# pcb_eagle.net
KiCad netlist of a schematic drawn in EAGLE
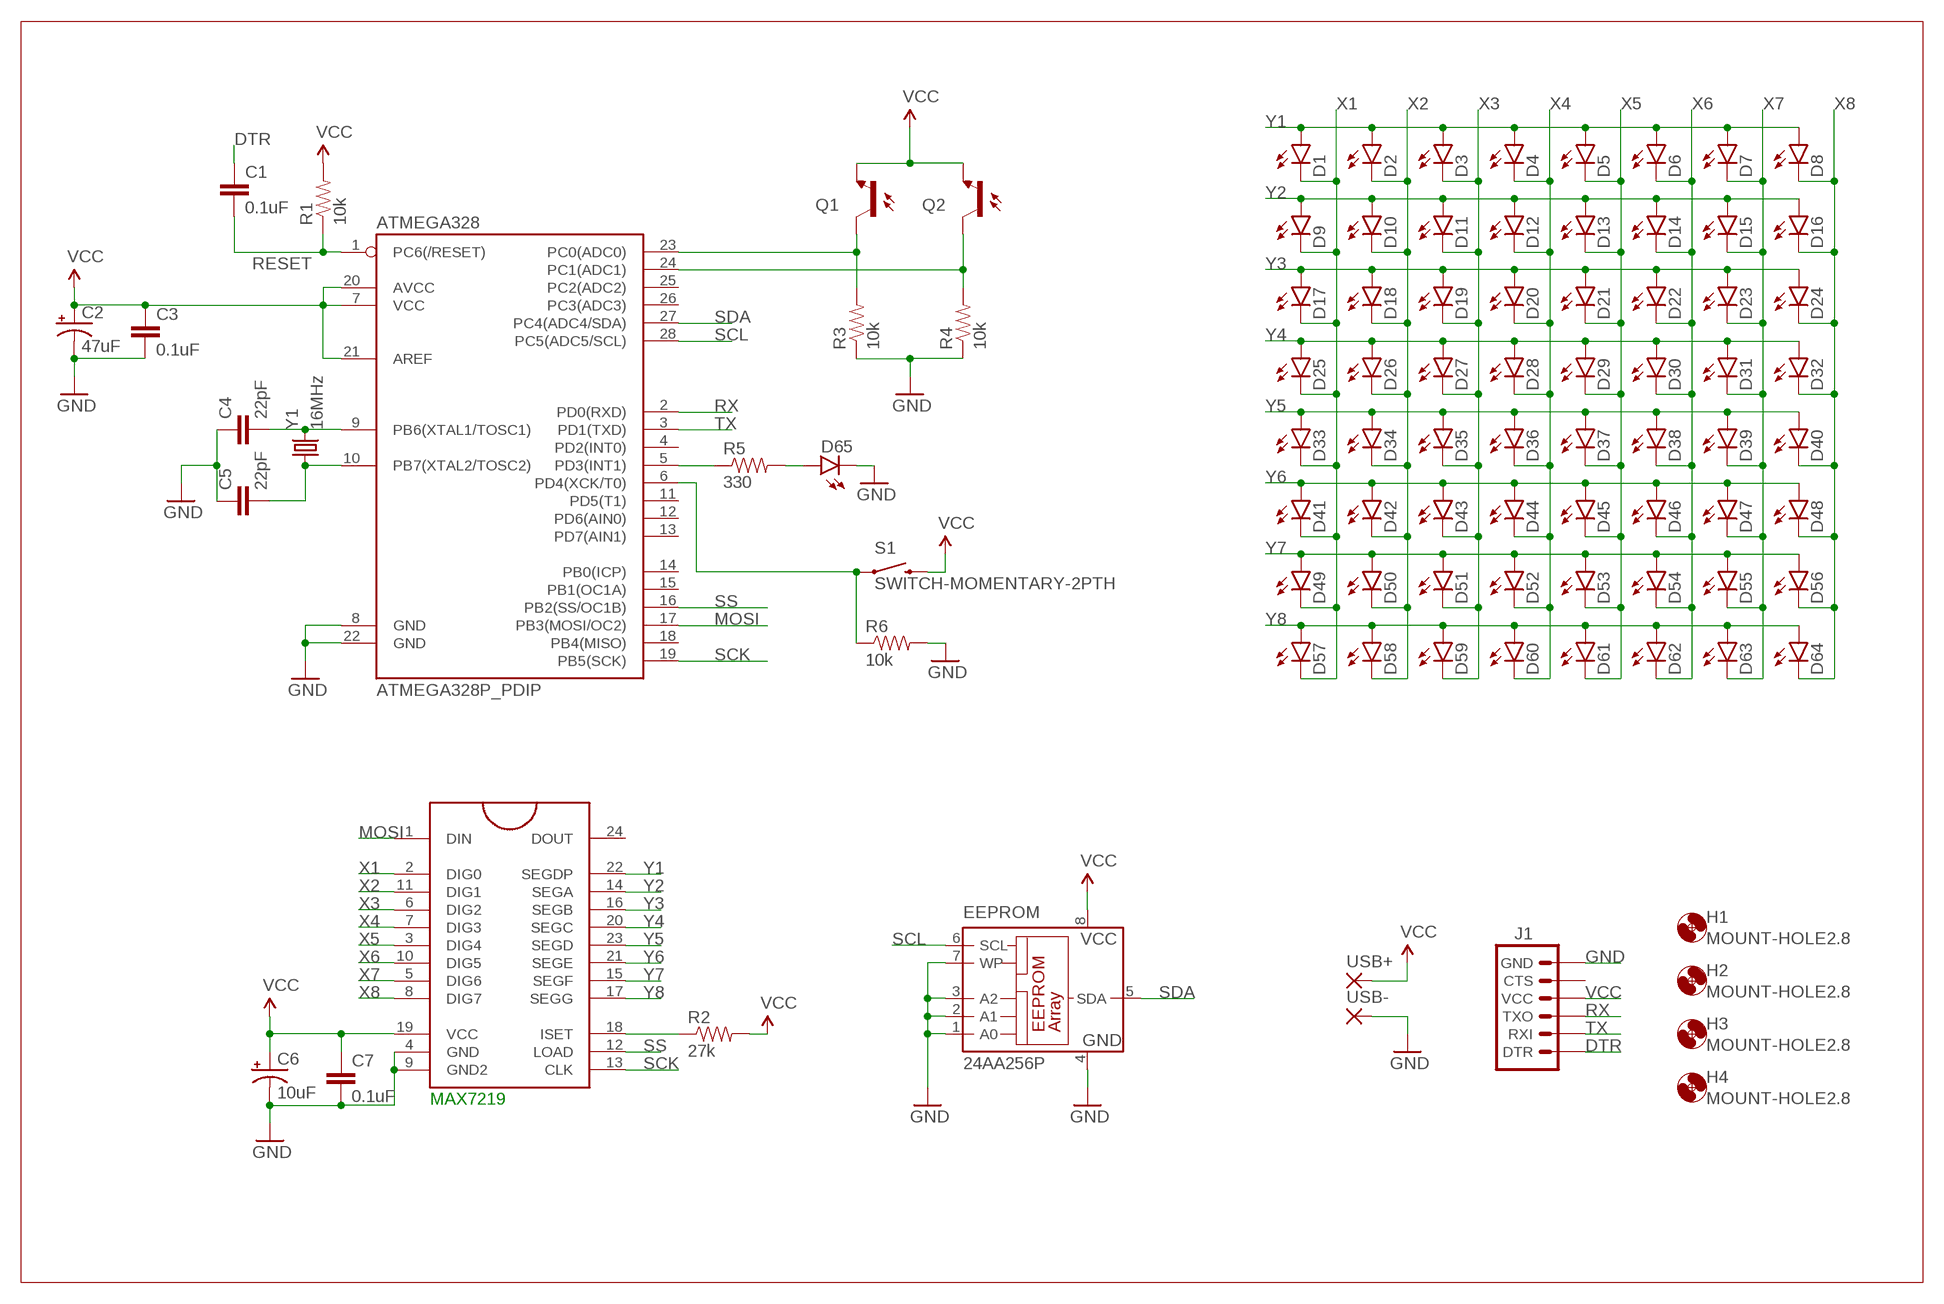
[diagram p0: schematic, sheet 1]

(export (version "E")
  (design (tool "Eeschema 10.0.6"))
  (components
    (comp (ref "ATMEGA328")
      (value "ATMEGA328P_PDIP")
      (footprint "eagle-import:DIL28-3")
      (libsource (lib "eagle-import") (part "ATMEGA328P_PDIP"))
    )
    (comp (ref "C1")
      (value "0.1uF")
      (footprint "eagle-import:CAP-PTH-SMALL")
      (libsource (lib "eagle-import") (part "CAPPTH"))
    )
    (comp (ref "C2")
      (value "47uF")
      (footprint "eagle-import:CPOL-RADIAL-10UF-25V")
      (libsource (lib "eagle-import") (part "CAP_POLPTH2"))
    )
    (comp (ref "C3")
      (value "0.1uF")
      (footprint "eagle-import:CAP-PTH-SMALL")
      (libsource (lib "eagle-import") (part "CAPPTH"))
    )
    (comp (ref "C4")
      (value "22pF")
      (footprint "eagle-import:CAP-PTH-SMALL")
      (libsource (lib "eagle-import") (part "CAPPTH"))
    )
    (comp (ref "C5")
      (value "22pF")
      (footprint "eagle-import:CAP-PTH-SMALL")
      (libsource (lib "eagle-import") (part "CAPPTH"))
    )
    (comp (ref "C6")
      (value "10uF")
      (footprint "eagle-import:CPOL-RADIAL-10UF-25V")
      (libsource (lib "eagle-import") (part "CAP_POLPTH2"))
    )
    (comp (ref "C7")
      (value "0.1uF")
      (footprint "eagle-import:CAP-PTH-SMALL")
      (libsource (lib "eagle-import") (part "CAPPTH"))
    )
    (comp (ref "D1")
      (value "LED3MM")
      (footprint "eagle-import:LED3MM")
      (libsource (lib "eagle-import") (part "LED3MM"))
    )
    (comp (ref "D2")
      (value "LED3MM")
      (footprint "eagle-import:LED3MM")
      (libsource (lib "eagle-import") (part "LED3MM"))
    )
    (comp (ref "D3")
      (value "LED3MM")
      (footprint "eagle-import:LED3MM")
      (libsource (lib "eagle-import") (part "LED3MM"))
    )
    (comp (ref "D4")
      (value "LED3MM")
      (footprint "eagle-import:LED3MM")
      (libsource (lib "eagle-import") (part "LED3MM"))
    )
    (comp (ref "D5")
      (value "LED3MM")
      (footprint "eagle-import:LED3MM")
      (libsource (lib "eagle-import") (part "LED3MM"))
    )
    (comp (ref "D6")
      (value "LED3MM")
      (footprint "eagle-import:LED3MM")
      (libsource (lib "eagle-import") (part "LED3MM"))
    )
    (comp (ref "D7")
      (value "LED3MM")
      (footprint "eagle-import:LED3MM")
      (libsource (lib "eagle-import") (part "LED3MM"))
    )
    (comp (ref "D8")
      (value "LED3MM")
      (footprint "eagle-import:LED3MM")
      (libsource (lib "eagle-import") (part "LED3MM"))
    )
    (comp (ref "D9")
      (value "LED3MM")
      (footprint "eagle-import:LED3MM")
      (libsource (lib "eagle-import") (part "LED3MM"))
    )
    (comp (ref "D10")
      (value "LED3MM")
      (footprint "eagle-import:LED3MM")
      (libsource (lib "eagle-import") (part "LED3MM"))
    )
    (comp (ref "D11")
      (value "LED3MM")
      (footprint "eagle-import:LED3MM")
      (libsource (lib "eagle-import") (part "LED3MM"))
    )
    (comp (ref "D12")
      (value "LED3MM")
      (footprint "eagle-import:LED3MM")
      (libsource (lib "eagle-import") (part "LED3MM"))
    )
    (comp (ref "D13")
      (value "LED3MM")
      (footprint "eagle-import:LED3MM")
      (libsource (lib "eagle-import") (part "LED3MM"))
    )
    (comp (ref "D14")
      (value "LED3MM")
      (footprint "eagle-import:LED3MM")
      (libsource (lib "eagle-import") (part "LED3MM"))
    )
    (comp (ref "D15")
      (value "LED3MM")
      (footprint "eagle-import:LED3MM")
      (libsource (lib "eagle-import") (part "LED3MM"))
    )
    (comp (ref "D16")
      (value "LED3MM")
      (footprint "eagle-import:LED3MM")
      (libsource (lib "eagle-import") (part "LED3MM"))
    )
    (comp (ref "D17")
      (value "LED3MM")
      (footprint "eagle-import:LED3MM")
      (libsource (lib "eagle-import") (part "LED3MM"))
    )
    (comp (ref "D18")
      (value "LED3MM")
      (footprint "eagle-import:LED3MM")
      (libsource (lib "eagle-import") (part "LED3MM"))
    )
    (comp (ref "D19")
      (value "LED3MM")
      (footprint "eagle-import:LED3MM")
      (libsource (lib "eagle-import") (part "LED3MM"))
    )
    (comp (ref "D20")
      (value "LED3MM")
      (footprint "eagle-import:LED3MM")
      (libsource (lib "eagle-import") (part "LED3MM"))
    )
    (comp (ref "D21")
      (value "LED3MM")
      (footprint "eagle-import:LED3MM")
      (libsource (lib "eagle-import") (part "LED3MM"))
    )
    (comp (ref "D22")
      (value "LED3MM")
      (footprint "eagle-import:LED3MM")
      (libsource (lib "eagle-import") (part "LED3MM"))
    )
    (comp (ref "D23")
      (value "LED3MM")
      (footprint "eagle-import:LED3MM")
      (libsource (lib "eagle-import") (part "LED3MM"))
    )
    (comp (ref "D24")
      (value "LED3MM")
      (footprint "eagle-import:LED3MM")
      (libsource (lib "eagle-import") (part "LED3MM"))
    )
    (comp (ref "D25")
      (value "LED3MM")
      (footprint "eagle-import:LED3MM")
      (libsource (lib "eagle-import") (part "LED3MM"))
    )
    (comp (ref "D26")
      (value "LED3MM")
      (footprint "eagle-import:LED3MM")
      (libsource (lib "eagle-import") (part "LED3MM"))
    )
    (comp (ref "D27")
      (value "LED3MM")
      (footprint "eagle-import:LED3MM")
      (libsource (lib "eagle-import") (part "LED3MM"))
    )
    (comp (ref "D28")
      (value "LED3MM")
      (footprint "eagle-import:LED3MM")
      (libsource (lib "eagle-import") (part "LED3MM"))
    )
    (comp (ref "D29")
      (value "LED3MM")
      (footprint "eagle-import:LED3MM")
      (libsource (lib "eagle-import") (part "LED3MM"))
    )
    (comp (ref "D30")
      (value "LED3MM")
      (footprint "eagle-import:LED3MM")
      (libsource (lib "eagle-import") (part "LED3MM"))
    )
    (comp (ref "D31")
      (value "LED3MM")
      (footprint "eagle-import:LED3MM")
      (libsource (lib "eagle-import") (part "LED3MM"))
    )
    (comp (ref "D32")
      (value "LED3MM")
      (footprint "eagle-import:LED3MM")
      (libsource (lib "eagle-import") (part "LED3MM"))
    )
    (comp (ref "D33")
      (value "LED3MM")
      (footprint "eagle-import:LED3MM")
      (libsource (lib "eagle-import") (part "LED3MM"))
    )
    (comp (ref "D34")
      (value "LED3MM")
      (footprint "eagle-import:LED3MM")
      (libsource (lib "eagle-import") (part "LED3MM"))
    )
    (comp (ref "D35")
      (value "LED3MM")
      (footprint "eagle-import:LED3MM")
      (libsource (lib "eagle-import") (part "LED3MM"))
    )
    (comp (ref "D36")
      (value "LED3MM")
      (footprint "eagle-import:LED3MM")
      (libsource (lib "eagle-import") (part "LED3MM"))
    )
    (comp (ref "D37")
      (value "LED3MM")
      (footprint "eagle-import:LED3MM")
      (libsource (lib "eagle-import") (part "LED3MM"))
    )
    (comp (ref "D38")
      (value "LED3MM")
      (footprint "eagle-import:LED3MM")
      (libsource (lib "eagle-import") (part "LED3MM"))
    )
    (comp (ref "D39")
      (value "LED3MM")
      (footprint "eagle-import:LED3MM")
      (libsource (lib "eagle-import") (part "LED3MM"))
    )
    (comp (ref "D40")
      (value "LED3MM")
      (footprint "eagle-import:LED3MM")
      (libsource (lib "eagle-import") (part "LED3MM"))
    )
    (comp (ref "D41")
      (value "LED3MM")
      (footprint "eagle-import:LED3MM")
      (libsource (lib "eagle-import") (part "LED3MM"))
    )
    (comp (ref "D42")
      (value "LED3MM")
      (footprint "eagle-import:LED3MM")
      (libsource (lib "eagle-import") (part "LED3MM"))
    )
    (comp (ref "D43")
      (value "LED3MM")
      (footprint "eagle-import:LED3MM")
      (libsource (lib "eagle-import") (part "LED3MM"))
    )
    (comp (ref "D44")
      (value "LED3MM")
      (footprint "eagle-import:LED3MM")
      (libsource (lib "eagle-import") (part "LED3MM"))
    )
    (comp (ref "D45")
      (value "LED3MM")
      (footprint "eagle-import:LED3MM")
      (libsource (lib "eagle-import") (part "LED3MM"))
    )
    (comp (ref "D46")
      (value "LED3MM")
      (footprint "eagle-import:LED3MM")
      (libsource (lib "eagle-import") (part "LED3MM"))
    )
    (comp (ref "D47")
      (value "LED3MM")
      (footprint "eagle-import:LED3MM")
      (libsource (lib "eagle-import") (part "LED3MM"))
    )
    (comp (ref "D48")
      (value "LED3MM")
      (footprint "eagle-import:LED3MM")
      (libsource (lib "eagle-import") (part "LED3MM"))
    )
    (comp (ref "D49")
      (value "LED3MM")
      (footprint "eagle-import:LED3MM")
      (libsource (lib "eagle-import") (part "LED3MM"))
    )
    (comp (ref "D50")
      (value "LED3MM")
      (footprint "eagle-import:LED3MM")
      (libsource (lib "eagle-import") (part "LED3MM"))
    )
    (comp (ref "D51")
      (value "LED3MM")
      (footprint "eagle-import:LED3MM")
      (libsource (lib "eagle-import") (part "LED3MM"))
    )
    (comp (ref "D52")
      (value "LED3MM")
      (footprint "eagle-import:LED3MM")
      (libsource (lib "eagle-import") (part "LED3MM"))
    )
    (comp (ref "D53")
      (value "LED3MM")
      (footprint "eagle-import:LED3MM")
      (libsource (lib "eagle-import") (part "LED3MM"))
    )
    (comp (ref "D54")
      (value "LED3MM")
      (footprint "eagle-import:LED3MM")
      (libsource (lib "eagle-import") (part "LED3MM"))
    )
    (comp (ref "D55")
      (value "LED3MM")
      (footprint "eagle-import:LED3MM")
      (libsource (lib "eagle-import") (part "LED3MM"))
    )
    (comp (ref "D56")
      (value "LED3MM")
      (footprint "eagle-import:LED3MM")
      (libsource (lib "eagle-import") (part "LED3MM"))
    )
    (comp (ref "D57")
      (value "LED3MM")
      (footprint "eagle-import:LED3MM")
      (libsource (lib "eagle-import") (part "LED3MM"))
    )
    (comp (ref "D58")
      (value "LED3MM")
      (footprint "eagle-import:LED3MM")
      (libsource (lib "eagle-import") (part "LED3MM"))
    )
    (comp (ref "D59")
      (value "LED3MM")
      (footprint "eagle-import:LED3MM")
      (libsource (lib "eagle-import") (part "LED3MM"))
    )
    (comp (ref "D60")
      (value "LED3MM")
      (footprint "eagle-import:LED3MM")
      (libsource (lib "eagle-import") (part "LED3MM"))
    )
    (comp (ref "D61")
      (value "LED3MM")
      (footprint "eagle-import:LED3MM")
      (libsource (lib "eagle-import") (part "LED3MM"))
    )
    (comp (ref "D62")
      (value "LED3MM")
      (footprint "eagle-import:LED3MM")
      (libsource (lib "eagle-import") (part "LED3MM"))
    )
    (comp (ref "D63")
      (value "LED3MM")
      (footprint "eagle-import:LED3MM")
      (libsource (lib "eagle-import") (part "LED3MM"))
    )
    (comp (ref "D64")
      (value "LED3MM")
      (footprint "eagle-import:LED3MM")
      (libsource (lib "eagle-import") (part "LED3MM"))
    )
    (comp (ref "D65")
      (value "LED3MM")
      (footprint "eagle-import:LED3MM")
      (libsource (lib "eagle-import") (part "LED3MM"))
    )
    (comp (ref "EEPROM")
      (value "24AA256P")
      (footprint "eagle-import:DIL8")
      (fields (field (name "MF") "MICROCHIP") (field (name "MPN") "24AA256-I/P"))
      (libsource (lib "eagle-import") (part "24PAA256"))
    )
    (comp (ref "H1")
      (value "MOUNT-HOLE2.8")
      (footprint "eagle-import:2,8")
      (libsource (lib "eagle-import") (part "MOUNT-HOLE2.8"))
    )
    (comp (ref "H2")
      (value "MOUNT-HOLE2.8")
      (footprint "eagle-import:2,8")
      (libsource (lib "eagle-import") (part "MOUNT-HOLE2.8"))
    )
    (comp (ref "H3")
      (value "MOUNT-HOLE2.8")
      (footprint "eagle-import:2,8")
      (libsource (lib "eagle-import") (part "MOUNT-HOLE2.8"))
    )
    (comp (ref "H4")
      (value "MOUNT-HOLE2.8")
      (footprint "eagle-import:2,8")
      (libsource (lib "eagle-import") (part "MOUNT-HOLE2.8"))
    )
    (comp (ref "J1")
      (value "ARDUINO_SERIAL_PROGRAMPTH")
      (footprint "eagle-import:1X06")
      (libsource (lib "eagle-import") (part "ARDUINO_SERIAL_PROGRAMPTH"))
    )
    (comp (ref "MAX72191")
      (value "MAX7219DIP")
      (footprint "eagle-import:DIL24")
      (libsource (lib "eagle-import") (part "MAX7219DIP"))
    )
    (comp (ref "Q1")
      (value "PHOTOTRANSISTORT1")
      (footprint "eagle-import:LED3MM")
      (libsource (lib "eagle-import") (part "PHOTOTRANSISTORT1"))
    )
    (comp (ref "Q2")
      (value "PHOTOTRANSISTORT1")
      (footprint "eagle-import:LED3MM")
      (libsource (lib "eagle-import") (part "PHOTOTRANSISTORT1"))
    )
    (comp (ref "R1")
      (value "10k")
      (footprint "eagle-import:AXIAL-0.3")
      (libsource (lib "eagle-import") (part "RESISTORAXIAL-0.3"))
    )
    (comp (ref "R2")
      (value "27k")
      (footprint "eagle-import:AXIAL-0.3")
      (libsource (lib "eagle-import") (part "SparkFun-Resistors_RESISTORAXIAL-0.3"))
    )
    (comp (ref "R3")
      (value "10k")
      (footprint "eagle-import:AXIAL-0.3")
      (libsource (lib "eagle-import") (part "RESISTORAXIAL-0.3"))
    )
    (comp (ref "R4")
      (value "10k")
      (footprint "eagle-import:AXIAL-0.3")
      (libsource (lib "eagle-import") (part "RESISTORAXIAL-0.3"))
    )
    (comp (ref "R5")
      (value "330")
      (footprint "eagle-import:AXIAL-0.3")
      (libsource (lib "eagle-import") (part "RESISTORAXIAL-0.3"))
    )
    (comp (ref "R6")
      (value "10k")
      (footprint "eagle-import:AXIAL-0.3")
      (libsource (lib "eagle-import") (part "RESISTORAXIAL-0.3"))
    )
    (comp (ref "S1")
      (value "SWITCH-MOMENTARY-2PTH")
      (footprint "eagle-import:TACTILE-PTH")
      (libsource (lib "eagle-import") (part "SWITCH-MOMENTARY-2PTH"))
    )
    (comp (ref "USB+")
      (value "2,54/0,9")
      (footprint "eagle-import:2,54_0,9")
      (libsource (lib "eagle-import") (part "2,54/0,9"))
    )
    (comp (ref "USB-")
      (value "2,54/0,9")
      (footprint "eagle-import:2,54_0,9")
      (libsource (lib "eagle-import") (part "2,54/0,9"))
    )
    (comp (ref "Y1")
      (value "16MHz")
      (footprint "eagle-import:HC49US")
      (libsource (lib "eagle-import") (part "CRYSTALHC49US"))
    )
  )
  (nets
    (net (code "1") (name "/DTR") (class "Default")
      (node (ref "C1") (pin "1") (pinfunction "1_1") (pintype "passive"))
      (node (ref "J1") (pin "1") (pinfunction "DTR_1") (pintype "passive"))
    )
    (net (code "2") (name "/MOSI") (class "Default")
      (node (ref "ATMEGA328") (pin "17") (pinfunction "PB3(MOSI/OC2)_17") (pintype "bidirectional"))
      (node (ref "MAX72191") (pin "1") (pinfunction "DIN_1") (pintype "bidirectional"))
    )
    (net (code "3") (name "/RESET") (class "Default")
      (node (ref "ATMEGA328") (pin "1") (pinfunction "PC6(/RESET)_1") (pintype "bidirectional"))
      (node (ref "C1") (pin "2") (pinfunction "2_2") (pintype "passive"))
      (node (ref "R1") (pin "P$1") (pinfunction "1_P$1") (pintype "passive"))
    )
    (net (code "4") (name "/RX") (class "Default")
      (node (ref "ATMEGA328") (pin "2") (pinfunction "PD0(RXD)_2") (pintype "bidirectional"))
      (node (ref "J1") (pin "3") (pinfunction "TXO_3") (pintype "passive"))
    )
    (net (code "5") (name "/SCK") (class "Default")
      (node (ref "ATMEGA328") (pin "19") (pinfunction "PB5(SCK)_19") (pintype "bidirectional"))
      (node (ref "MAX72191") (pin "13") (pinfunction "CLK_13") (pintype "bidirectional"))
    )
    (net (code "6") (name "/SCL") (class "Default")
      (node (ref "ATMEGA328") (pin "28") (pinfunction "PC5(ADC5/SCL)_28") (pintype "bidirectional"))
      (node (ref "EEPROM") (pin "6") (pinfunction "SCL_6") (pintype "input"))
    )
    (net (code "7") (name "/SDA") (class "Default")
      (node (ref "ATMEGA328") (pin "27") (pinfunction "PC4(ADC4/SDA)_27") (pintype "bidirectional"))
      (node (ref "EEPROM") (pin "5") (pinfunction "SDA_5") (pintype "bidirectional"))
    )
    (net (code "8") (name "/SS") (class "Default")
      (node (ref "ATMEGA328") (pin "16") (pinfunction "PB2(SS/OC1B)_16") (pintype "bidirectional"))
      (node (ref "MAX72191") (pin "12") (pinfunction "LOAD_12") (pintype "bidirectional"))
    )
    (net (code "9") (name "/TX") (class "Default")
      (node (ref "ATMEGA328") (pin "3") (pinfunction "PD1(TXD)_3") (pintype "bidirectional"))
      (node (ref "J1") (pin "2") (pinfunction "RXI_2") (pintype "passive"))
    )
    (net (code "10") (name "/X1") (class "Default")
      (node (ref "D1") (pin "K") (pinfunction "C_K") (pintype "passive"))
      (node (ref "D17") (pin "K") (pinfunction "C_K") (pintype "passive"))
      (node (ref "D25") (pin "K") (pinfunction "C_K") (pintype "passive"))
      (node (ref "D33") (pin "K") (pinfunction "C_K") (pintype "passive"))
      (node (ref "D41") (pin "K") (pinfunction "C_K") (pintype "passive"))
      (node (ref "D49") (pin "K") (pinfunction "C_K") (pintype "passive"))
      (node (ref "D57") (pin "K") (pinfunction "C_K") (pintype "passive"))
      (node (ref "D9") (pin "K") (pinfunction "C_K") (pintype "passive"))
      (node (ref "MAX72191") (pin "2") (pinfunction "DIG0_2") (pintype "bidirectional"))
    )
    (net (code "11") (name "/X2") (class "Default")
      (node (ref "D10") (pin "K") (pinfunction "C_K") (pintype "passive"))
      (node (ref "D18") (pin "K") (pinfunction "C_K") (pintype "passive"))
      (node (ref "D2") (pin "K") (pinfunction "C_K") (pintype "passive"))
      (node (ref "D26") (pin "K") (pinfunction "C_K") (pintype "passive"))
      (node (ref "D34") (pin "K") (pinfunction "C_K") (pintype "passive"))
      (node (ref "D42") (pin "K") (pinfunction "C_K") (pintype "passive"))
      (node (ref "D50") (pin "K") (pinfunction "C_K") (pintype "passive"))
      (node (ref "D58") (pin "K") (pinfunction "C_K") (pintype "passive"))
      (node (ref "MAX72191") (pin "11") (pinfunction "DIG1_11") (pintype "bidirectional"))
    )
    (net (code "12") (name "/X3") (class "Default")
      (node (ref "D11") (pin "K") (pinfunction "C_K") (pintype "passive"))
      (node (ref "D19") (pin "K") (pinfunction "C_K") (pintype "passive"))
      (node (ref "D27") (pin "K") (pinfunction "C_K") (pintype "passive"))
      (node (ref "D3") (pin "K") (pinfunction "C_K") (pintype "passive"))
      (node (ref "D35") (pin "K") (pinfunction "C_K") (pintype "passive"))
      (node (ref "D43") (pin "K") (pinfunction "C_K") (pintype "passive"))
      (node (ref "D51") (pin "K") (pinfunction "C_K") (pintype "passive"))
      (node (ref "D59") (pin "K") (pinfunction "C_K") (pintype "passive"))
      (node (ref "MAX72191") (pin "6") (pinfunction "DIG2_6") (pintype "bidirectional"))
    )
    (net (code "13") (name "/X4") (class "Default")
      (node (ref "D12") (pin "K") (pinfunction "C_K") (pintype "passive"))
      (node (ref "D20") (pin "K") (pinfunction "C_K") (pintype "passive"))
      (node (ref "D28") (pin "K") (pinfunction "C_K") (pintype "passive"))
      (node (ref "D36") (pin "K") (pinfunction "C_K") (pintype "passive"))
      (node (ref "D4") (pin "K") (pinfunction "C_K") (pintype "passive"))
      (node (ref "D44") (pin "K") (pinfunction "C_K") (pintype "passive"))
      (node (ref "D52") (pin "K") (pinfunction "C_K") (pintype "passive"))
      (node (ref "D60") (pin "K") (pinfunction "C_K") (pintype "passive"))
      (node (ref "MAX72191") (pin "7") (pinfunction "DIG3_7") (pintype "bidirectional"))
    )
    (net (code "14") (name "/X5") (class "Default")
      (node (ref "D13") (pin "K") (pinfunction "C_K") (pintype "passive"))
      (node (ref "D21") (pin "K") (pinfunction "C_K") (pintype "passive"))
      (node (ref "D29") (pin "K") (pinfunction "C_K") (pintype "passive"))
      (node (ref "D37") (pin "K") (pinfunction "C_K") (pintype "passive"))
      (node (ref "D45") (pin "K") (pinfunction "C_K") (pintype "passive"))
      (node (ref "D5") (pin "K") (pinfunction "C_K") (pintype "passive"))
      (node (ref "D53") (pin "K") (pinfunction "C_K") (pintype "passive"))
      (node (ref "D61") (pin "K") (pinfunction "C_K") (pintype "passive"))
      (node (ref "MAX72191") (pin "3") (pinfunction "DIG4_3") (pintype "bidirectional"))
    )
    (net (code "15") (name "/X6") (class "Default")
      (node (ref "D14") (pin "K") (pinfunction "C_K") (pintype "passive"))
      (node (ref "D22") (pin "K") (pinfunction "C_K") (pintype "passive"))
      (node (ref "D30") (pin "K") (pinfunction "C_K") (pintype "passive"))
      (node (ref "D38") (pin "K") (pinfunction "C_K") (pintype "passive"))
      (node (ref "D46") (pin "K") (pinfunction "C_K") (pintype "passive"))
      (node (ref "D54") (pin "K") (pinfunction "C_K") (pintype "passive"))
      (node (ref "D6") (pin "K") (pinfunction "C_K") (pintype "passive"))
      (node (ref "D62") (pin "K") (pinfunction "C_K") (pintype "passive"))
      (node (ref "MAX72191") (pin "10") (pinfunction "DIG5_10") (pintype "bidirectional"))
    )
    (net (code "16") (name "/X7") (class "Default")
      (node (ref "D15") (pin "K") (pinfunction "C_K") (pintype "passive"))
      (node (ref "D23") (pin "K") (pinfunction "C_K") (pintype "passive"))
      (node (ref "D31") (pin "K") (pinfunction "C_K") (pintype "passive"))
      (node (ref "D39") (pin "K") (pinfunction "C_K") (pintype "passive"))
      (node (ref "D47") (pin "K") (pinfunction "C_K") (pintype "passive"))
      (node (ref "D55") (pin "K") (pinfunction "C_K") (pintype "passive"))
      (node (ref "D63") (pin "K") (pinfunction "C_K") (pintype "passive"))
      (node (ref "D7") (pin "K") (pinfunction "C_K") (pintype "passive"))
      (node (ref "MAX72191") (pin "5") (pinfunction "DIG6_5") (pintype "bidirectional"))
    )
    (net (code "17") (name "/X8") (class "Default")
      (node (ref "D16") (pin "K") (pinfunction "C_K") (pintype "passive"))
      (node (ref "D24") (pin "K") (pinfunction "C_K") (pintype "passive"))
      (node (ref "D32") (pin "K") (pinfunction "C_K") (pintype "passive"))
      (node (ref "D40") (pin "K") (pinfunction "C_K") (pintype "passive"))
      (node (ref "D48") (pin "K") (pinfunction "C_K") (pintype "passive"))
      (node (ref "D56") (pin "K") (pinfunction "C_K") (pintype "passive"))
      (node (ref "D64") (pin "K") (pinfunction "C_K") (pintype "passive"))
      (node (ref "D8") (pin "K") (pinfunction "C_K") (pintype "passive"))
      (node (ref "MAX72191") (pin "8") (pinfunction "DIG7_8") (pintype "bidirectional"))
    )
    (net (code "18") (name "/Y1") (class "Default")
      (node (ref "D1") (pin "A") (pinfunction "A_A") (pintype "passive"))
      (node (ref "D2") (pin "A") (pinfunction "A_A") (pintype "passive"))
      (node (ref "D3") (pin "A") (pinfunction "A_A") (pintype "passive"))
      (node (ref "D4") (pin "A") (pinfunction "A_A") (pintype "passive"))
      (node (ref "D5") (pin "A") (pinfunction "A_A") (pintype "passive"))
      (node (ref "D6") (pin "A") (pinfunction "A_A") (pintype "passive"))
      (node (ref "D7") (pin "A") (pinfunction "A_A") (pintype "passive"))
      (node (ref "D8") (pin "A") (pinfunction "A_A") (pintype "passive"))
      (node (ref "MAX72191") (pin "22") (pinfunction "SEGDP_22") (pintype "bidirectional"))
    )
    (net (code "19") (name "/Y2") (class "Default")
      (node (ref "D10") (pin "A") (pinfunction "A_A") (pintype "passive"))
      (node (ref "D11") (pin "A") (pinfunction "A_A") (pintype "passive"))
      (node (ref "D12") (pin "A") (pinfunction "A_A") (pintype "passive"))
      (node (ref "D13") (pin "A") (pinfunction "A_A") (pintype "passive"))
      (node (ref "D14") (pin "A") (pinfunction "A_A") (pintype "passive"))
      (node (ref "D15") (pin "A") (pinfunction "A_A") (pintype "passive"))
      (node (ref "D16") (pin "A") (pinfunction "A_A") (pintype "passive"))
      (node (ref "D9") (pin "A") (pinfunction "A_A") (pintype "passive"))
      (node (ref "MAX72191") (pin "14") (pinfunction "SEGA_14") (pintype "bidirectional"))
    )
    (net (code "20") (name "/Y3") (class "Default")
      (node (ref "D17") (pin "A") (pinfunction "A_A") (pintype "passive"))
      (node (ref "D18") (pin "A") (pinfunction "A_A") (pintype "passive"))
      (node (ref "D19") (pin "A") (pinfunction "A_A") (pintype "passive"))
      (node (ref "D20") (pin "A") (pinfunction "A_A") (pintype "passive"))
      (node (ref "D21") (pin "A") (pinfunction "A_A") (pintype "passive"))
      (node (ref "D22") (pin "A") (pinfunction "A_A") (pintype "passive"))
      (node (ref "D23") (pin "A") (pinfunction "A_A") (pintype "passive"))
      (node (ref "D24") (pin "A") (pinfunction "A_A") (pintype "passive"))
      (node (ref "MAX72191") (pin "16") (pinfunction "SEGB_16") (pintype "bidirectional"))
    )
    (net (code "21") (name "/Y4") (class "Default")
      (node (ref "D25") (pin "A") (pinfunction "A_A") (pintype "passive"))
      (node (ref "D26") (pin "A") (pinfunction "A_A") (pintype "passive"))
      (node (ref "D27") (pin "A") (pinfunction "A_A") (pintype "passive"))
      (node (ref "D28") (pin "A") (pinfunction "A_A") (pintype "passive"))
      (node (ref "D29") (pin "A") (pinfunction "A_A") (pintype "passive"))
      (node (ref "D30") (pin "A") (pinfunction "A_A") (pintype "passive"))
      (node (ref "D31") (pin "A") (pinfunction "A_A") (pintype "passive"))
      (node (ref "D32") (pin "A") (pinfunction "A_A") (pintype "passive"))
      (node (ref "MAX72191") (pin "20") (pinfunction "SEGC_20") (pintype "bidirectional"))
    )
    (net (code "22") (name "/Y5") (class "Default")
      (node (ref "D33") (pin "A") (pinfunction "A_A") (pintype "passive"))
      (node (ref "D34") (pin "A") (pinfunction "A_A") (pintype "passive"))
      (node (ref "D35") (pin "A") (pinfunction "A_A") (pintype "passive"))
      (node (ref "D36") (pin "A") (pinfunction "A_A") (pintype "passive"))
      (node (ref "D37") (pin "A") (pinfunction "A_A") (pintype "passive"))
      (node (ref "D38") (pin "A") (pinfunction "A_A") (pintype "passive"))
      (node (ref "D39") (pin "A") (pinfunction "A_A") (pintype "passive"))
      (node (ref "D40") (pin "A") (pinfunction "A_A") (pintype "passive"))
      (node (ref "MAX72191") (pin "23") (pinfunction "SEGD_23") (pintype "bidirectional"))
    )
    (net (code "23") (name "/Y6") (class "Default")
      (node (ref "D41") (pin "A") (pinfunction "A_A") (pintype "passive"))
      (node (ref "D42") (pin "A") (pinfunction "A_A") (pintype "passive"))
      (node (ref "D43") (pin "A") (pinfunction "A_A") (pintype "passive"))
      (node (ref "D44") (pin "A") (pinfunction "A_A") (pintype "passive"))
      (node (ref "D45") (pin "A") (pinfunction "A_A") (pintype "passive"))
      (node (ref "D46") (pin "A") (pinfunction "A_A") (pintype "passive"))
      (node (ref "D47") (pin "A") (pinfunction "A_A") (pintype "passive"))
      (node (ref "D48") (pin "A") (pinfunction "A_A") (pintype "passive"))
      (node (ref "MAX72191") (pin "21") (pinfunction "SEGE_21") (pintype "bidirectional"))
    )
    (net (code "24") (name "/Y7") (class "Default")
      (node (ref "D49") (pin "A") (pinfunction "A_A") (pintype "passive"))
      (node (ref "D50") (pin "A") (pinfunction "A_A") (pintype "passive"))
      (node (ref "D51") (pin "A") (pinfunction "A_A") (pintype "passive"))
      (node (ref "D52") (pin "A") (pinfunction "A_A") (pintype "passive"))
      (node (ref "D53") (pin "A") (pinfunction "A_A") (pintype "passive"))
      (node (ref "D54") (pin "A") (pinfunction "A_A") (pintype "passive"))
      (node (ref "D55") (pin "A") (pinfunction "A_A") (pintype "passive"))
      (node (ref "D56") (pin "A") (pinfunction "A_A") (pintype "passive"))
      (node (ref "MAX72191") (pin "15") (pinfunction "SEGF_15") (pintype "bidirectional"))
    )
    (net (code "25") (name "/Y8") (class "Default")
      (node (ref "D57") (pin "A") (pinfunction "A_A") (pintype "passive"))
      (node (ref "D58") (pin "A") (pinfunction "A_A") (pintype "passive"))
      (node (ref "D59") (pin "A") (pinfunction "A_A") (pintype "passive"))
      (node (ref "D60") (pin "A") (pinfunction "A_A") (pintype "passive"))
      (node (ref "D61") (pin "A") (pinfunction "A_A") (pintype "passive"))
      (node (ref "D62") (pin "A") (pinfunction "A_A") (pintype "passive"))
      (node (ref "D63") (pin "A") (pinfunction "A_A") (pintype "passive"))
      (node (ref "D64") (pin "A") (pinfunction "A_A") (pintype "passive"))
      (node (ref "MAX72191") (pin "17") (pinfunction "SEGG_17") (pintype "bidirectional"))
    )
    (net (code "26") (name "GND") (class "Default")
      (node (ref "ATMEGA328") (pin "22") (pinfunction "GND_22") (pintype "bidirectional"))
      (node (ref "ATMEGA328") (pin "8") (pinfunction "GND_8") (pintype "bidirectional"))
      (node (ref "C2") (pin "2") (pinfunction "-_2") (pintype "passive"))
      (node (ref "C3") (pin "2") (pinfunction "2_2") (pintype "passive"))
      (node (ref "C4") (pin "1") (pinfunction "1_1") (pintype "passive"))
      (node (ref "C5") (pin "1") (pinfunction "1_1") (pintype "passive"))
      (node (ref "C6") (pin "2") (pinfunction "-_2") (pintype "passive"))
      (node (ref "C7") (pin "2") (pinfunction "2_2") (pintype "passive"))
      (node (ref "D65") (pin "K") (pinfunction "C_K") (pintype "passive"))
      (node (ref "EEPROM") (pin "1") (pinfunction "A0_1") (pintype "input"))
      (node (ref "EEPROM") (pin "2") (pinfunction "A1_2") (pintype "input"))
      (node (ref "EEPROM") (pin "3") (pinfunction "A2_3") (pintype "input"))
      (node (ref "EEPROM") (pin "4") (pinfunction "GND_4") (pintype "power_in"))
      (node (ref "EEPROM") (pin "7") (pinfunction "WP_7") (pintype "input"))
      (node (ref "J1") (pin "6") (pinfunction "GND_6") (pintype "passive"))
      (node (ref "MAX72191") (pin "4") (pinfunction "GND_4") (pintype "bidirectional"))
      (node (ref "MAX72191") (pin "9") (pinfunction "GND2_9") (pintype "bidirectional"))
      (node (ref "R3") (pin "P$1") (pinfunction "1_P$1") (pintype "passive"))
      (node (ref "R4") (pin "P$1") (pinfunction "1_P$1") (pintype "passive"))
      (node (ref "R6") (pin "P$2") (pinfunction "2_P$2") (pintype "passive"))
      (node (ref "USB-") (pin "1") (pinfunction "P_1") (pintype "passive"))
    )
    (net (code "27") (name "Net-(ATMEGA328-PB6(XTAL1{slash}TOSC1))") (class "Default")
      (node (ref "ATMEGA328") (pin "9") (pinfunction "PB6(XTAL1/TOSC1)_9") (pintype "bidirectional"))
      (node (ref "C4") (pin "2") (pinfunction "2_2") (pintype "passive"))
      (node (ref "Y1") (pin "2") (pinfunction "2_2") (pintype "passive"))
    )
    (net (code "28") (name "Net-(ATMEGA328-PB7(XTAL2{slash}TOSC2))") (class "Default")
      (node (ref "ATMEGA328") (pin "10") (pinfunction "PB7(XTAL2/TOSC2)_10") (pintype "bidirectional"))
      (node (ref "C5") (pin "2") (pinfunction "2_2") (pintype "passive"))
      (node (ref "Y1") (pin "1") (pinfunction "1_1") (pintype "passive"))
    )
    (net (code "29") (name "Net-(ATMEGA328-PC0(ADC0))") (class "Default")
      (node (ref "ATMEGA328") (pin "23") (pinfunction "PC0(ADC0)_23") (pintype "bidirectional"))
      (node (ref "Q1") (pin "C") (pinfunction "C_C") (pintype "passive"))
      (node (ref "R3") (pin "P$2") (pinfunction "2_P$2") (pintype "passive"))
    )
    (net (code "30") (name "Net-(ATMEGA328-PC1(ADC1))") (class "Default")
      (node (ref "ATMEGA328") (pin "24") (pinfunction "PC1(ADC1)_24") (pintype "bidirectional"))
      (node (ref "Q2") (pin "C") (pinfunction "C_C") (pintype "passive"))
      (node (ref "R4") (pin "P$2") (pinfunction "2_P$2") (pintype "passive"))
    )
    (net (code "31") (name "Net-(ATMEGA328-PD3(INT1))") (class "Default")
      (node (ref "ATMEGA328") (pin "5") (pinfunction "PD3(INT1)_5") (pintype "bidirectional"))
      (node (ref "R5") (pin "P$1") (pinfunction "1_P$1") (pintype "passive"))
    )
    (net (code "32") (name "Net-(ATMEGA328-PD4(XCK{slash}T0))") (class "Default")
      (node (ref "ATMEGA328") (pin "6") (pinfunction "PD4(XCK/T0)_6") (pintype "bidirectional"))
      (node (ref "R6") (pin "P$1") (pinfunction "1_P$1") (pintype "passive"))
      (node (ref "S1") (pin "1") (pinfunction "1_1") (pintype "passive"))
    )
    (net (code "33") (name "Net-(MAX72191-ISET)") (class "Default")
      (node (ref "MAX72191") (pin "18") (pinfunction "ISET_18") (pintype "bidirectional"))
      (node (ref "R2") (pin "P$1") (pinfunction "1_P$1") (pintype "passive"))
    )
    (net (code "34") (name "Net-(R5-2)") (class "Default")
      (node (ref "D65") (pin "A") (pinfunction "A_A") (pintype "passive"))
      (node (ref "R5") (pin "P$2") (pinfunction "2_P$2") (pintype "passive"))
    )
    (net (code "35") (name "VCC") (class "Default")
      (node (ref "ATMEGA328") (pin "20") (pinfunction "AVCC_20") (pintype "bidirectional"))
      (node (ref "ATMEGA328") (pin "21") (pinfunction "AREF_21") (pintype "bidirectional"))
      (node (ref "ATMEGA328") (pin "7") (pinfunction "VCC_7") (pintype "bidirectional"))
      (node (ref "C2") (pin "1") (pinfunction "+_1") (pintype "passive"))
      (node (ref "C3") (pin "1") (pinfunction "1_1") (pintype "passive"))
      (node (ref "C6") (pin "1") (pinfunction "+_1") (pintype "passive"))
      (node (ref "C7") (pin "1") (pinfunction "1_1") (pintype "passive"))
      (node (ref "EEPROM") (pin "8") (pinfunction "VCC_8") (pintype "power_in"))
      (node (ref "J1") (pin "4") (pinfunction "VCC_4") (pintype "passive"))
      (node (ref "MAX72191") (pin "19") (pinfunction "VCC_19") (pintype "bidirectional"))
      (node (ref "Q1") (pin "E") (pinfunction "E_E") (pintype "passive"))
      (node (ref "Q2") (pin "E") (pinfunction "E_E") (pintype "passive"))
      (node (ref "R1") (pin "P$2") (pinfunction "2_P$2") (pintype "passive"))
      (node (ref "R2") (pin "P$2") (pinfunction "2_P$2") (pintype "passive"))
      (node (ref "S1") (pin "3") (pinfunction "2_3") (pintype "passive"))
      (node (ref "USB+") (pin "1") (pinfunction "P_1") (pintype "passive"))
    )
    (net (code "36") (name "unconnected-(ATMEGA328-PB0(ICP)-Pad14)") (class "Default")
      (node (ref "ATMEGA328") (pin "14") (pinfunction "PB0(ICP)_14") (pintype "bidirectional"))
    )
    (net (code "37") (name "unconnected-(ATMEGA328-PB1(OC1A)-Pad15)") (class "Default")
      (node (ref "ATMEGA328") (pin "15") (pinfunction "PB1(OC1A)_15") (pintype "bidirectional"))
    )
    (net (code "38") (name "unconnected-(ATMEGA328-PB4(MISO)-Pad18)") (class "Default")
      (node (ref "ATMEGA328") (pin "18") (pinfunction "PB4(MISO)_18") (pintype "bidirectional"))
    )
    (net (code "39") (name "unconnected-(ATMEGA328-PC2(ADC2)-Pad25)") (class "Default")
      (node (ref "ATMEGA328") (pin "25") (pinfunction "PC2(ADC2)_25") (pintype "bidirectional"))
    )
    (net (code "40") (name "unconnected-(ATMEGA328-PC3(ADC3)-Pad26)") (class "Default")
      (node (ref "ATMEGA328") (pin "26") (pinfunction "PC3(ADC3)_26") (pintype "bidirectional"))
    )
    (net (code "41") (name "unconnected-(ATMEGA328-PD2(INT0)-Pad4)") (class "Default")
      (node (ref "ATMEGA328") (pin "4") (pinfunction "PD2(INT0)_4") (pintype "bidirectional"))
    )
    (net (code "42") (name "unconnected-(ATMEGA328-PD5(T1)-Pad11)") (class "Default")
      (node (ref "ATMEGA328") (pin "11") (pinfunction "PD5(T1)_11") (pintype "bidirectional"))
    )
    (net (code "43") (name "unconnected-(ATMEGA328-PD6(AIN0)-Pad12)") (class "Default")
      (node (ref "ATMEGA328") (pin "12") (pinfunction "PD6(AIN0)_12") (pintype "bidirectional"))
    )
    (net (code "44") (name "unconnected-(ATMEGA328-PD7(AIN1)-Pad13)") (class "Default")
      (node (ref "ATMEGA328") (pin "13") (pinfunction "PD7(AIN1)_13") (pintype "bidirectional"))
    )
    (net (code "45") (name "unconnected-(J1-CTS-Pad5)") (class "Default")
      (node (ref "J1") (pin "5") (pinfunction "CTS_5") (pintype "passive"))
    )
    (net (code "46") (name "unconnected-(MAX72191-DOUT-Pad24)") (class "Default")
      (node (ref "MAX72191") (pin "24") (pinfunction "DOUT_24") (pintype "bidirectional"))
    )
  )
)
